# khoi_he_thong.net
KiCad netlist of a schematic drawn in Altium Designer
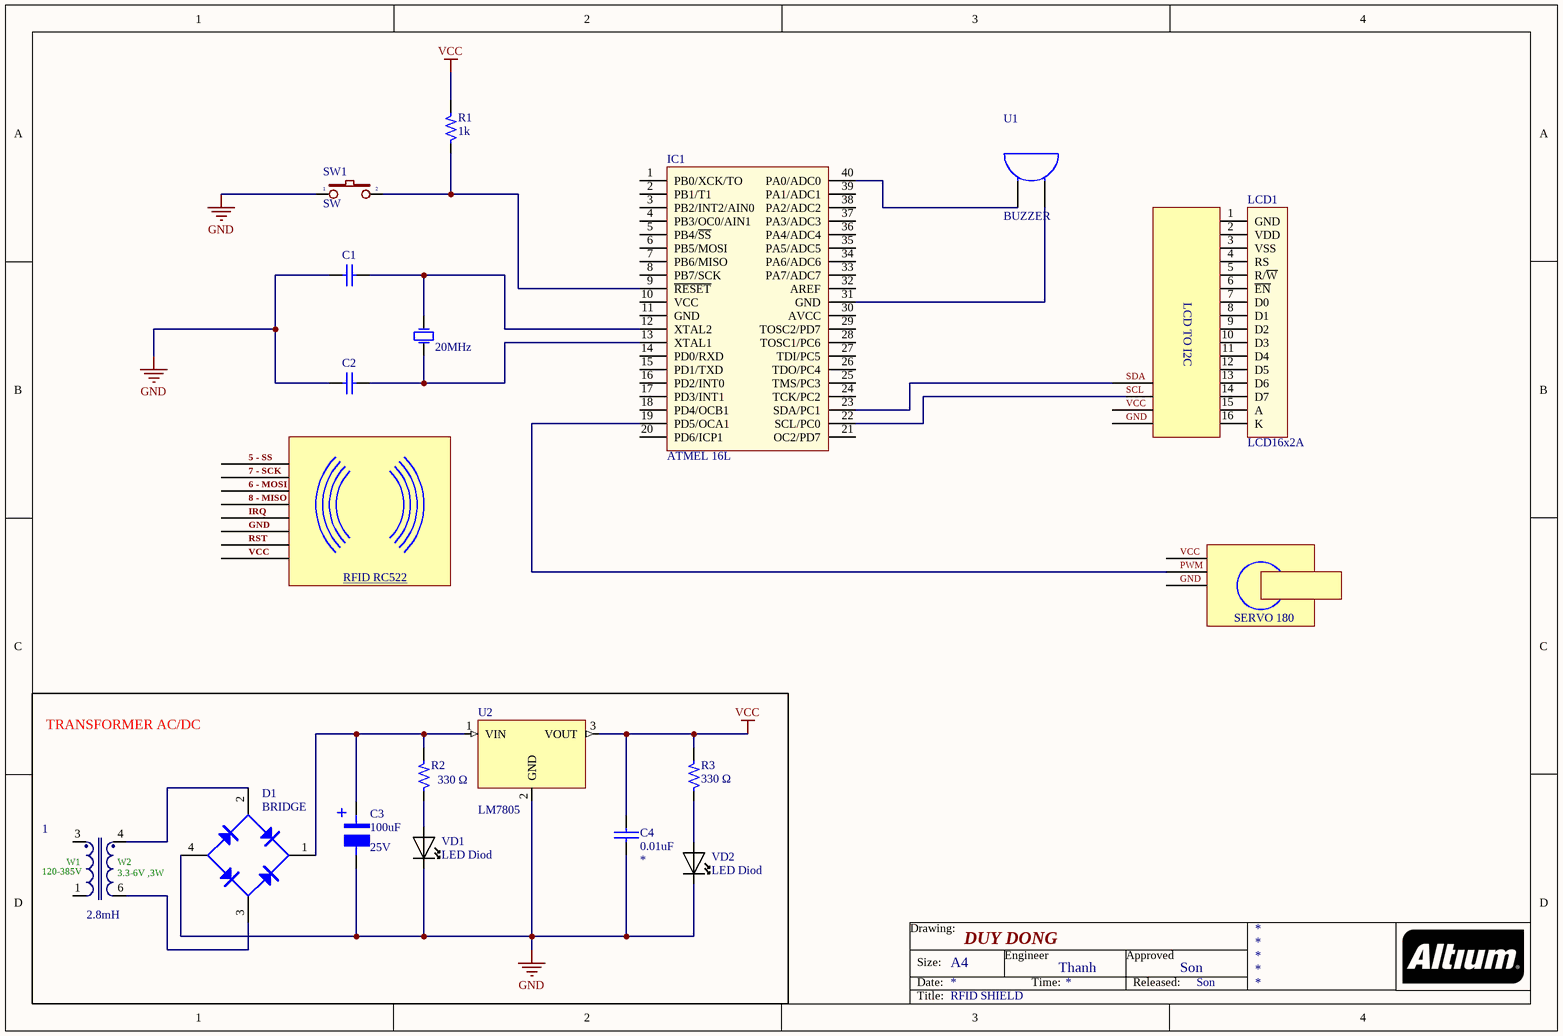
[diagram p0: khoi_he_thong.SchDoc]

(export (version "E")
  (design (tool "Eeschema 10.0.6"))
  (components
    (comp (ref "1")
      (value "2.8mH")
      (footprint "EE13/7/4-Vertical/(EF12.6)")
      (description "Off-Line Transformer WE-UNIT , L=2.8mH")
      (fields
        (field (name "PARTNO") "749118105")
        (field (name "MANUFACTURER") "Würth Elektronik eiSos GmbH")
        (field (name "CREATED BY") "Otto Christin")
      )
      (libsource (lib "KhanhBK_SCH_Library_1") (part "Tranf5"))
    )
    (comp (ref "C1")
      (value "~")
      (footprint "103/2KV")
      (description "Capacitor Ceramic 2KV")
      (fields (field (name "PUBLISHER") "Altium Limited"))
      (libsource (lib "Cty1") (part "Cap2KV"))
    )
    (comp (ref "C2")
      (value "~")
      (footprint "103/2KV")
      (description "Capacitor Ceramic 2KV")
      (fields (field (name "PUBLISHER") "Altium Limited"))
      (libsource (lib "Cty1") (part "Cap2KV"))
    )
    (comp (ref "C3")
      (value "100uF")
      (footprint "Cty1:Cap100uFx50V")
      (libsource (lib "Cty1") (part "Cap100uF 50V"))
    )
    (comp (ref "C4")
      (value "0.01uF")
      (footprint "*")
      (description "Capacitor")
      (libsource (lib "Cty1") (part "CAP"))
    )
    (comp (ref "D1")
      (value "BRIDGE")
      (footprint "BRIDGE_DAN")
      (description "Diode Bridge")
      (libsource (lib "Cty1") (part "BRIDGE1"))
    )
    (comp (ref "IC1")
      (value "ATMEL 16L")
      (footprint "DIP40/W0.6")
      (description "8-Bit AVR Microcontroller with 16K Bytes of In-System Programmable Flash Memory")
      (libsource (lib "Cty1") (part "Atmega16L"))
    )
    (comp (ref "LCD1")
      (value "LCD16x2A")
      (footprint "LCD16X2")
      (description "LCD dipslay 16 char, 2 line")
      (libsource (lib "Cty1") (part "LCD16x2"))
    )
    (comp (ref "R1")
      (value "1k")
      (footprint "R1/6W")
      (description "Resistor 1/4W")
      (libsource (lib "Cty1") (part "Res"))
    )
    (comp (ref "R2")
      (value "330 Ω")
      (footprint "R1/6W")
      (description "Resistor 1/4W")
      (libsource (lib "Cty1") (part "Res"))
    )
    (comp (ref "R3")
      (value "330 Ω")
      (footprint "R1/6W")
      (description "Resistor 1/4W")
      (libsource (lib "Cty1") (part "Res"))
    )
    (comp (ref "SW1")
      (value "SW")
      (footprint "SW2")
      (description "Switch button 2 pin")
      (libsource (lib "Cty1") (part "SW2"))
    )
    (comp (ref "U1") (value "BUZZER") (description "Buzzer") (libsource (lib "Cty1") (part "BUZZER")))
    (comp (ref "U2")
      (value "LM7805")
      (footprint "TO-220")
      (description "TO-220")
      (libsource (lib "Cty1") (part "LM7805"))
    )
    (comp (ref "VD1") (value "LED Diod") (libsource (lib "Cty1") (part "LED Diod")))
    (comp (ref "VD2") (value "LED Diod") (libsource (lib "Cty1") (part "LED Diod")))
    (comp (ref "Y1")
      (value "20MHz")
      (footprint "XT2")
      (description "Crystal Oscillator")
      (fields (field (name "PUBLISHER") "Altium Limited"))
      (libsource (lib "Cty1") (part "Crystal"))
    )
  )
  (nets
    (net (code "8") (name "/SCL") (class "Default")
      (node (ref "IC1") (pin "22") (pinfunction "SCL/PC0_22") (pintype "passive"))
    )
    (net (code "10") (name "GND") (class "Default")
      (node (ref "C1") (pin "1") (pinfunction "1_1") (pintype "passive"))
      (node (ref "C2") (pin "1") (pinfunction "1_1") (pintype "passive"))
      (node (ref "C3") (pin "2") (pinfunction "2_2") (pintype "passive"))
      (node (ref "C4") (pin "2") (pinfunction "2_2") (pintype "passive"))
      (node (ref "D1") (pin "4") (pinfunction "V-_4") (pintype "passive"))
      (node (ref "SW1") (pin "1") (pinfunction "1_1") (pintype "passive"))
      (node (ref "U2") (pin "2") (pinfunction "GND_2") (pintype "power_in"))
      (node (ref "VD1") (pin "K") (pinfunction "2_K") (pintype "passive"))
      (node (ref "VD2") (pin "K") (pinfunction "2_K") (pintype "passive"))
    )
    (net (code "11") (name "Net-(1-Pad4)") (class "Default")
      (node (ref "1") (pin "4") (pinfunction "4_4") (pintype "passive"))
      (node (ref "D1") (pin "2") (pinfunction "AC_2") (pintype "passive"))
    )
    (net (code "12") (name "Net-(1-Pad6)") (class "Default")
      (node (ref "1") (pin "6") (pinfunction "6_6") (pintype "passive"))
      (node (ref "D1") (pin "3") (pinfunction "AC_3") (pintype "passive"))
    )
    (net (code "13") (name "Net-(D1-V+)") (class "Default")
      (node (ref "C3") (pin "1") (pinfunction "1_1") (pintype "passive"))
      (node (ref "D1") (pin "1") (pinfunction "V+_1") (pintype "passive"))
      (node (ref "R2") (pin "2") (pinfunction "2_2") (pintype "passive"))
      (node (ref "U2") (pin "1") (pinfunction "VIN_1") (pintype "input"))
    )
    (net (code "14") (name "Net-(IC1-PA0{slash}ADC0)") (class "Default")
      (node (ref "IC1") (pin "40") (pinfunction "PA0/ADC0_40") (pintype "passive"))
      (node (ref "U1") (pin "1") (pinfunction "A_1") (pintype "passive"))
    )
    (net (code "15") (name "Net-(IC1-XTAL1)") (class "Default")
      (node (ref "C2") (pin "2") (pinfunction "2_2") (pintype "passive"))
      (node (ref "IC1") (pin "13") (pinfunction "XTAL1_13") (pintype "passive"))
      (node (ref "Y1") (pin "1") (pinfunction "OSC1_1") (pintype "passive"))
    )
    (net (code "16") (name "Net-(IC1-XTAL2)") (class "Default")
      (node (ref "C1") (pin "2") (pinfunction "2_2") (pintype "passive"))
      (node (ref "IC1") (pin "12") (pinfunction "XTAL2_12") (pintype "passive"))
      (node (ref "Y1") (pin "2") (pinfunction "OSC2_2") (pintype "passive"))
    )
    (net (code "17") (name "Net-(IC1-~{RESET})") (class "Default")
      (node (ref "IC1") (pin "9") (pinfunction "~{RESET}_9") (pintype "passive"))
      (node (ref "R1") (pin "1") (pinfunction "1_1") (pintype "passive"))
      (node (ref "SW1") (pin "2") (pinfunction "2_2") (pintype "passive"))
    )
    (net (code "18") (name "Net-(U1-B)") (class "Default")
      (node (ref "IC1") (pin "31") (pinfunction "GND_31") (pintype "passive"))
      (node (ref "U1") (pin "2") (pinfunction "B_2") (pintype "passive"))
    )
    (net (code "19") (name "Net-(VD1-1)") (class "Default")
      (node (ref "R2") (pin "1") (pinfunction "1_1") (pintype "passive"))
      (node (ref "VD1") (pin "A") (pinfunction "1_A") (pintype "passive"))
    )
    (net (code "20") (name "Net-(VD2-1)") (class "Default")
      (node (ref "R3") (pin "1") (pinfunction "1_1") (pintype "passive"))
      (node (ref "VD2") (pin "A") (pinfunction "1_A") (pintype "passive"))
    )
    (net (code "21") (name "VCC") (class "Default")
      (node (ref "C4") (pin "1") (pinfunction "1_1") (pintype "passive"))
      (node (ref "R1") (pin "2") (pinfunction "2_2") (pintype "passive"))
      (node (ref "R3") (pin "2") (pinfunction "2_2") (pintype "passive"))
      (node (ref "U2") (pin "3") (pinfunction "VOUT_3") (pintype "output"))
    )
    (net (code "22") (name "unconnected-(1-Pad1)") (class "Default")
      (node (ref "1") (pin "1") (pinfunction "1_1") (pintype "passive"))
    )
    (net (code "23") (name "unconnected-(1-Pad3)") (class "Default")
      (node (ref "1") (pin "3") (pinfunction "3_3") (pintype "passive"))
    )
    (net (code "24") (name "unconnected-(IC1-AREF-Pad32)") (class "Default")
      (node (ref "IC1") (pin "32") (pinfunction "AREF_32") (pintype "passive"))
    )
    (net (code "25") (name "unconnected-(IC1-AVCC-Pad30)") (class "Default")
      (node (ref "IC1") (pin "30") (pinfunction "AVCC_30") (pintype "passive"))
    )
    (net (code "26") (name "unconnected-(IC1-GND-Pad11)") (class "Default")
      (node (ref "IC1") (pin "11") (pinfunction "GND_11") (pintype "passive"))
    )
    (net (code "27") (name "unconnected-(IC1-OC2{slash}PD7-Pad21)") (class "Default")
      (node (ref "IC1") (pin "21") (pinfunction "OC2/PD7_21") (pintype "passive"))
    )
    (net (code "28") (name "unconnected-(IC1-PA1{slash}ADC1-Pad39)") (class "Default")
      (node (ref "IC1") (pin "39") (pinfunction "PA1/ADC1_39") (pintype "passive"))
    )
    (net (code "29") (name "unconnected-(IC1-PA2{slash}ADC2-Pad38)") (class "Default")
      (node (ref "IC1") (pin "38") (pinfunction "PA2/ADC2_38") (pintype "passive"))
    )
    (net (code "30") (name "unconnected-(IC1-PA3{slash}ADC3-Pad37)") (class "Default")
      (node (ref "IC1") (pin "37") (pinfunction "PA3/ADC3_37") (pintype "passive"))
    )
    (net (code "31") (name "unconnected-(IC1-PA4{slash}ADC4-Pad36)") (class "Default")
      (node (ref "IC1") (pin "36") (pinfunction "PA4/ADC4_36") (pintype "passive"))
    )
    (net (code "32") (name "unconnected-(IC1-PA5{slash}ADC5-Pad35)") (class "Default")
      (node (ref "IC1") (pin "35") (pinfunction "PA5/ADC5_35") (pintype "passive"))
    )
    (net (code "33") (name "unconnected-(IC1-PA6{slash}ADC6-Pad34)") (class "Default")
      (node (ref "IC1") (pin "34") (pinfunction "PA6/ADC6_34") (pintype "passive"))
    )
    (net (code "34") (name "unconnected-(IC1-PA7{slash}ADC7-Pad33)") (class "Default")
      (node (ref "IC1") (pin "33") (pinfunction "PA7/ADC7_33") (pintype "passive"))
    )
    (net (code "35") (name "unconnected-(IC1-PB0{slash}XCK{slash}TO-Pad1)") (class "Default")
      (node (ref "IC1") (pin "1") (pinfunction "PB0/XCK/TO_1") (pintype "passive"))
    )
    (net (code "36") (name "unconnected-(IC1-PB1{slash}T1-Pad2)") (class "Default")
      (node (ref "IC1") (pin "2") (pinfunction "PB1/T1_2") (pintype "passive"))
    )
    (net (code "37") (name "unconnected-(IC1-PB2{slash}INT2{slash}AIN0-Pad3)") (class "Default")
      (node (ref "IC1") (pin "3") (pinfunction "PB2/INT2/AIN0_3") (pintype "passive"))
    )
    (net (code "38") (name "unconnected-(IC1-PB3{slash}OC0{slash}AIN1-Pad4)") (class "Default")
      (node (ref "IC1") (pin "4") (pinfunction "PB3/OC0/AIN1_4") (pintype "passive"))
    )
    (net (code "39") (name "unconnected-(IC1-PB4{slash}~{SS}-Pad5)") (class "Default")
      (node (ref "IC1") (pin "5") (pinfunction "PB4/~{SS}_5") (pintype "passive"))
    )
    (net (code "40") (name "unconnected-(IC1-PB5{slash}MOSI-Pad6)") (class "Default")
      (node (ref "IC1") (pin "6") (pinfunction "PB5/MOSI_6") (pintype "passive"))
    )
    (net (code "41") (name "unconnected-(IC1-PB6{slash}MISO-Pad7)") (class "Default")
      (node (ref "IC1") (pin "7") (pinfunction "PB6/MISO_7") (pintype "passive"))
    )
    (net (code "42") (name "unconnected-(IC1-PB7{slash}SCK-Pad8)") (class "Default")
      (node (ref "IC1") (pin "8") (pinfunction "PB7/SCK_8") (pintype "passive"))
    )
    (net (code "43") (name "unconnected-(IC1-PD0{slash}RXD-Pad14)") (class "Default")
      (node (ref "IC1") (pin "14") (pinfunction "PD0/RXD_14") (pintype "passive"))
    )
    (net (code "44") (name "unconnected-(IC1-PD1{slash}TXD-Pad15)") (class "Default")
      (node (ref "IC1") (pin "15") (pinfunction "PD1/TXD_15") (pintype "passive"))
    )
    (net (code "45") (name "unconnected-(IC1-PD2{slash}INT0-Pad16)") (class "Default")
      (node (ref "IC1") (pin "16") (pinfunction "PD2/INT0_16") (pintype "passive"))
    )
    (net (code "46") (name "unconnected-(IC1-PD3{slash}INT1-Pad17)") (class "Default")
      (node (ref "IC1") (pin "17") (pinfunction "PD3/INT1_17") (pintype "passive"))
    )
    (net (code "47") (name "unconnected-(IC1-PD4{slash}OCB1-Pad18)") (class "Default")
      (node (ref "IC1") (pin "18") (pinfunction "PD4/OCB1_18") (pintype "passive"))
    )
    (net (code "48") (name "unconnected-(IC1-PD5{slash}OCA1-Pad19)") (class "Default")
      (node (ref "IC1") (pin "19") (pinfunction "PD5/OCA1_19") (pintype "passive"))
    )
    (net (code "49") (name "unconnected-(IC1-PD6{slash}ICP1-Pad20)") (class "Default")
      (node (ref "IC1") (pin "20") (pinfunction "PD6/ICP1_20") (pintype "passive"))
    )
    (net (code "50") (name "unconnected-(IC1-SDA{slash}PC1-Pad23)") (class "Default")
      (node (ref "IC1") (pin "23") (pinfunction "SDA/PC1_23") (pintype "passive"))
    )
    (net (code "51") (name "unconnected-(IC1-TCK{slash}PC2-Pad24)") (class "Default")
      (node (ref "IC1") (pin "24") (pinfunction "TCK/PC2_24") (pintype "passive"))
    )
    (net (code "52") (name "unconnected-(IC1-TDI{slash}PC5-Pad27)") (class "Default")
      (node (ref "IC1") (pin "27") (pinfunction "TDI/PC5_27") (pintype "passive"))
    )
    (net (code "53") (name "unconnected-(IC1-TDO{slash}PC4-Pad26)") (class "Default")
      (node (ref "IC1") (pin "26") (pinfunction "TDO/PC4_26") (pintype "passive"))
    )
    (net (code "54") (name "unconnected-(IC1-TMS{slash}PC3-Pad25)") (class "Default")
      (node (ref "IC1") (pin "25") (pinfunction "TMS/PC3_25") (pintype "passive"))
    )
    (net (code "55") (name "unconnected-(IC1-TOSC1{slash}PC6-Pad28)") (class "Default")
      (node (ref "IC1") (pin "28") (pinfunction "TOSC1/PC6_28") (pintype "passive"))
    )
    (net (code "56") (name "unconnected-(IC1-TOSC2{slash}PD7-Pad29)") (class "Default")
      (node (ref "IC1") (pin "29") (pinfunction "TOSC2/PD7_29") (pintype "passive"))
    )
    (net (code "57") (name "unconnected-(IC1-VCC-Pad10)") (class "Default")
      (node (ref "IC1") (pin "10") (pinfunction "VCC_10") (pintype "passive"))
    )
    (net (code "58") (name "unconnected-(LCD1-A-Pad15)") (class "Default")
      (node (ref "LCD1") (pin "15") (pinfunction "A_15") (pintype "passive"))
    )
    (net (code "59") (name "unconnected-(LCD1-D0-Pad7)") (class "Default")
      (node (ref "LCD1") (pin "7") (pinfunction "D0_7") (pintype "passive"))
    )
    (net (code "60") (name "unconnected-(LCD1-D1-Pad8)") (class "Default")
      (node (ref "LCD1") (pin "8") (pinfunction "D1_8") (pintype "passive"))
    )
    (net (code "61") (name "unconnected-(LCD1-D2-Pad9)") (class "Default")
      (node (ref "LCD1") (pin "9") (pinfunction "D2_9") (pintype "passive"))
    )
    (net (code "62") (name "unconnected-(LCD1-D3-Pad10)") (class "Default")
      (node (ref "LCD1") (pin "10") (pinfunction "D3_10") (pintype "passive"))
    )
    (net (code "63") (name "unconnected-(LCD1-D4-Pad11)") (class "Default")
      (node (ref "LCD1") (pin "11") (pinfunction "D4_11") (pintype "passive"))
    )
    (net (code "64") (name "unconnected-(LCD1-D5-Pad12)") (class "Default")
      (node (ref "LCD1") (pin "12") (pinfunction "D5_12") (pintype "passive"))
    )
    (net (code "65") (name "unconnected-(LCD1-D6-Pad13)") (class "Default")
      (node (ref "LCD1") (pin "13") (pinfunction "D6_13") (pintype "passive"))
    )
    (net (code "66") (name "unconnected-(LCD1-D7-Pad14)") (class "Default")
      (node (ref "LCD1") (pin "14") (pinfunction "D7_14") (pintype "passive"))
    )
    (net (code "67") (name "unconnected-(LCD1-GND-Pad1)") (class "Default")
      (node (ref "LCD1") (pin "1") (pinfunction "GND_1") (pintype "passive"))
    )
    (net (code "68") (name "unconnected-(LCD1-K-Pad16)") (class "Default")
      (node (ref "LCD1") (pin "16") (pinfunction "K_16") (pintype "passive"))
    )
    (net (code "69") (name "unconnected-(LCD1-RS-Pad4)") (class "Default")
      (node (ref "LCD1") (pin "4") (pinfunction "RS_4") (pintype "passive"))
    )
    (net (code "70") (name "unconnected-(LCD1-R{slash}~{W}-Pad5)") (class "Default")
      (node (ref "LCD1") (pin "5") (pinfunction "R/~{W}_5") (pintype "passive"))
    )
    (net (code "71") (name "unconnected-(LCD1-VDD-Pad2)") (class "Default")
      (node (ref "LCD1") (pin "2") (pinfunction "VDD_2") (pintype "passive"))
    )
    (net (code "72") (name "unconnected-(LCD1-VSS-Pad3)") (class "Default")
      (node (ref "LCD1") (pin "3") (pinfunction "VSS_3") (pintype "passive"))
    )
    (net (code "73") (name "unconnected-(LCD1-~{EN}-Pad6)") (class "Default")
      (node (ref "LCD1") (pin "6") (pinfunction "~{EN}_6") (pintype "passive"))
    )
  )
)
